# 2_PowerPerif.net
KiCad netlist of a schematic drawn in Altium Designer
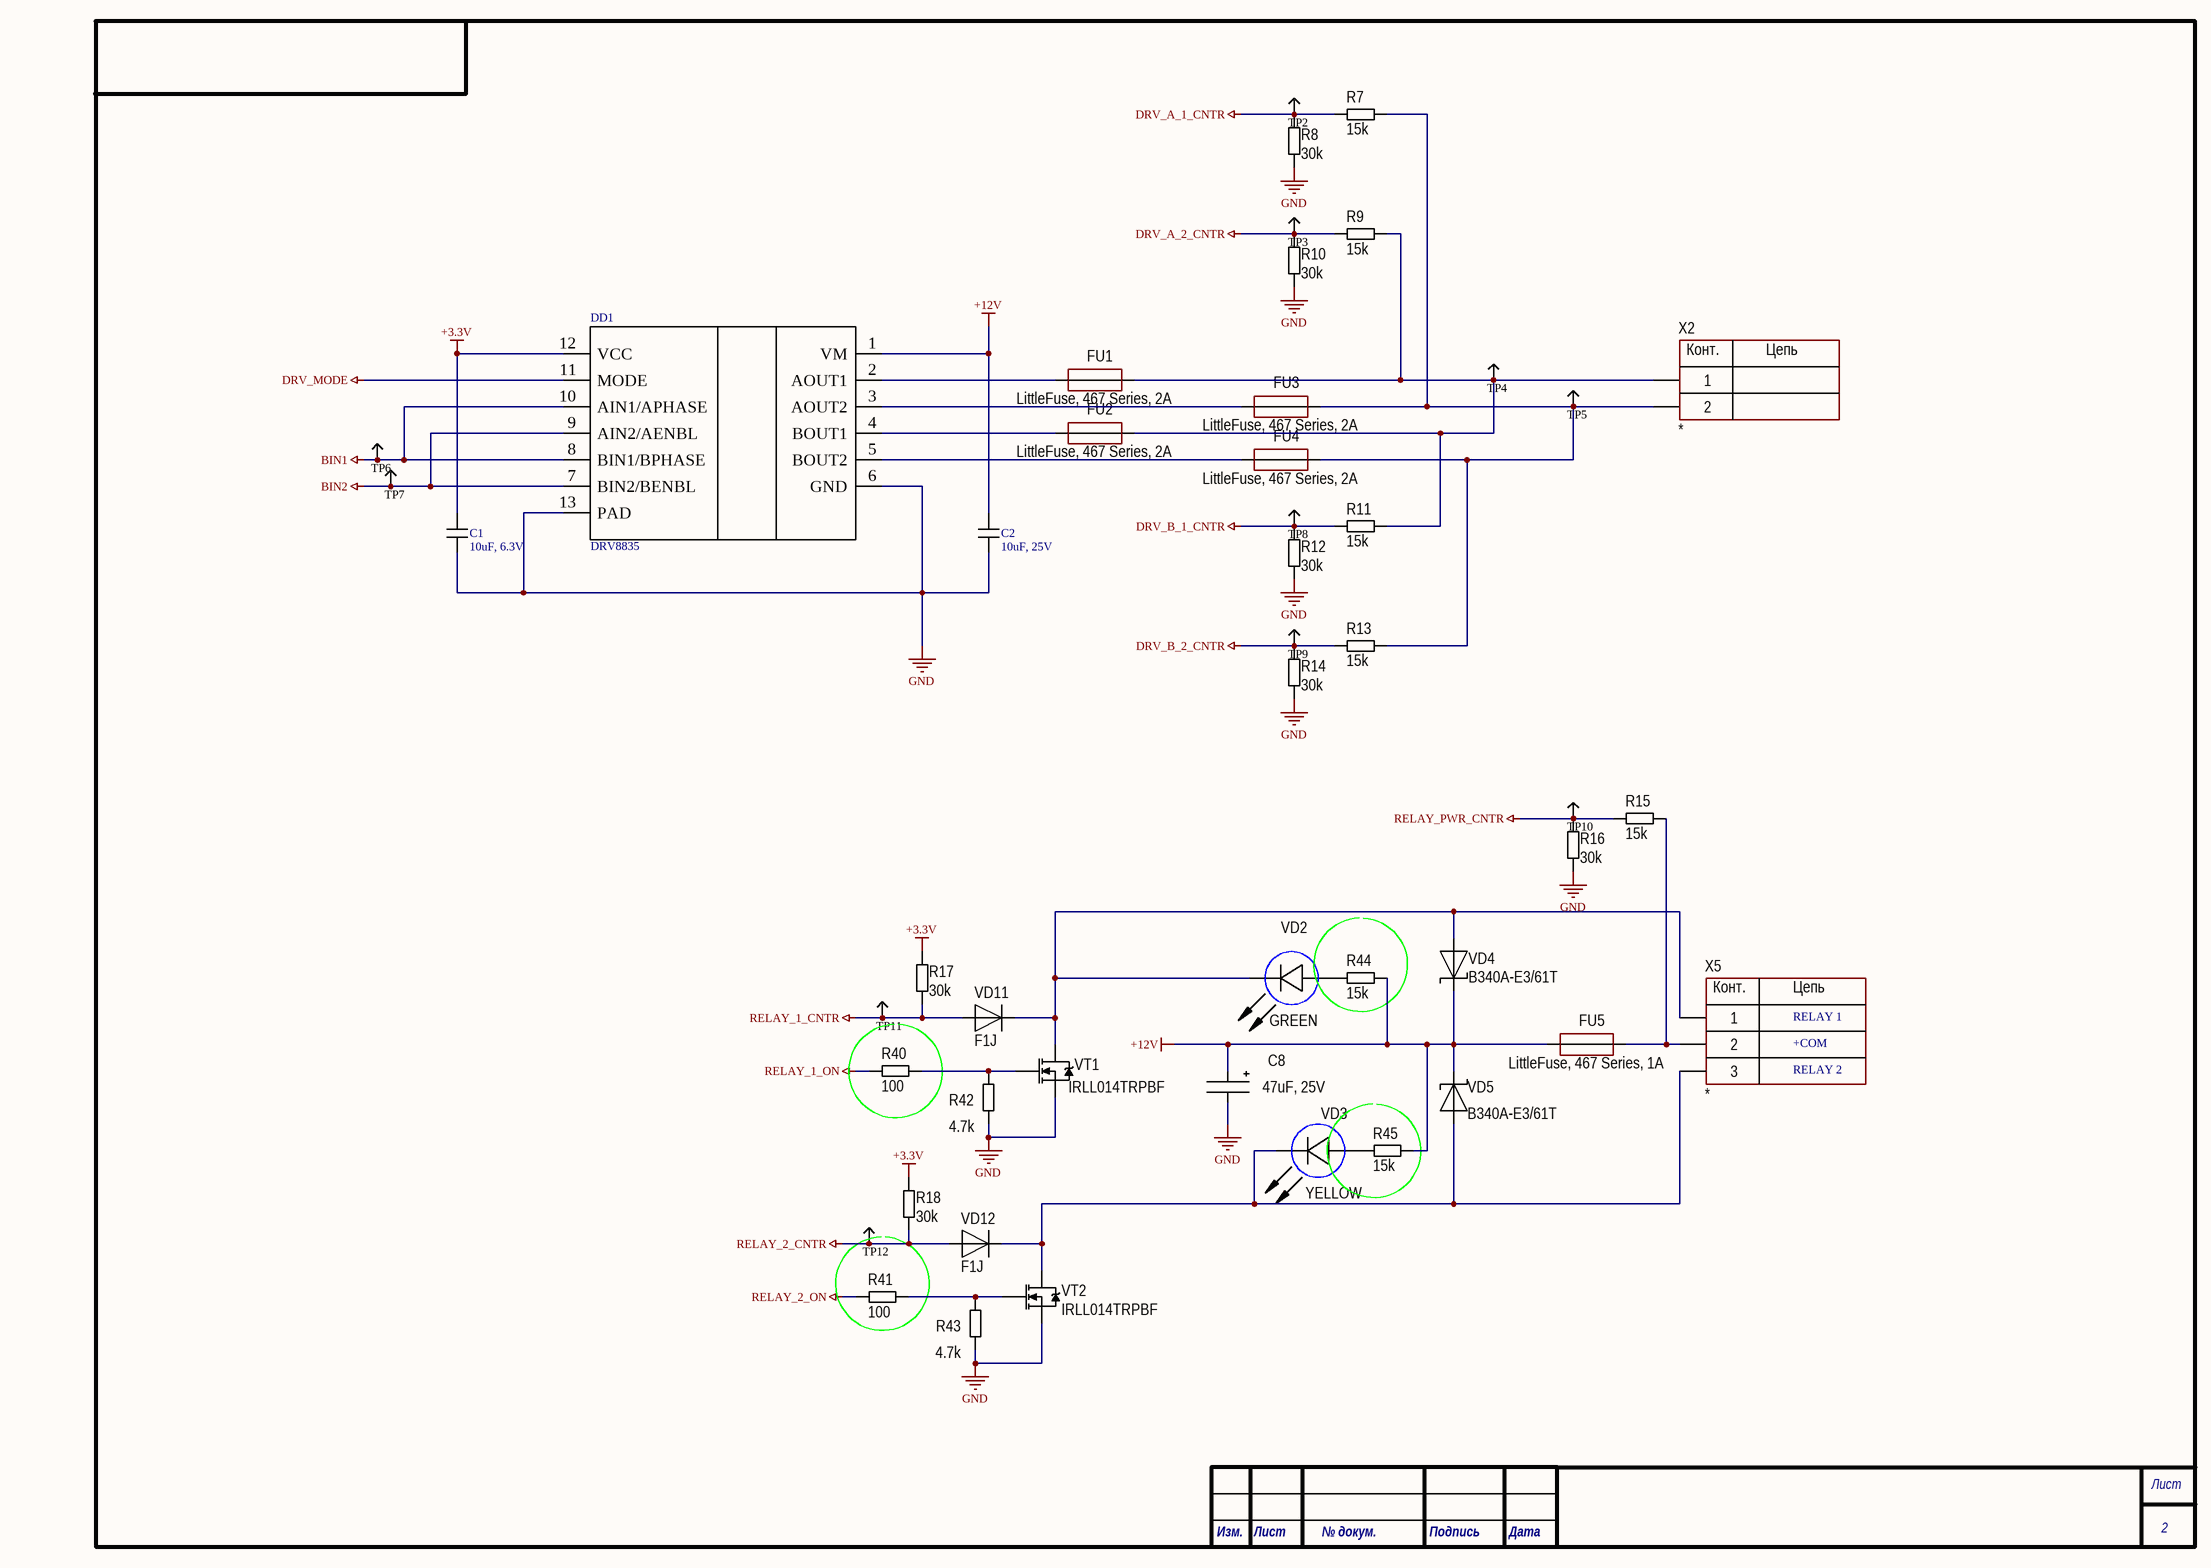
[diagram p0: 2_PowerPerif.SchDoc]

(export (version "E")
  (design (tool "Eeschema 10.0.6"))
  (components
    (comp (ref "C1")
      (value "10uF, 6.3V")
      (footprint "C_0603")
      (libsource (lib "Condensators") (part "C_SMD"))
    )
    (comp (ref "C2") (value "10uF, 25V") (footprint "C_0603") (libsource (lib "Condensators") (part "C_SMD")))
    (comp (ref "C8")
      (value "47uF, 25V")
      (footprint "D8C3.2H12")
      (libsource (lib "Condensators") (part "AlumCap"))
    )
    (comp (ref "DD1")
      (value "DRV8835")
      (footprint "WSON12")
      (description "Driver")
      (libsource (lib "MicroIC") (part "DRV8835"))
    )
    (comp (ref "FU1")
      (value "LittleFuse, 467 Series, 2A")
      (footprint "CH0603F")
      (libsource (lib "Melochi") (part "Fuse"))
    )
    (comp (ref "FU2")
      (value "LittleFuse, 467 Series, 2A")
      (footprint "CH0603F")
      (libsource (lib "Melochi") (part "Fuse"))
    )
    (comp (ref "FU3")
      (value "LittleFuse, 467 Series, 2A")
      (footprint "CH0603F")
      (libsource (lib "Melochi") (part "Fuse"))
    )
    (comp (ref "FU4")
      (value "LittleFuse, 467 Series, 2A")
      (footprint "CH0603F")
      (libsource (lib "Melochi") (part "Fuse"))
    )
    (comp (ref "FU5")
      (value "LittleFuse, 467 Series, 1A")
      (footprint "CH0603F")
      (libsource (lib "Melochi") (part "Fuse"))
    )
    (comp (ref "R7") (value "15k") (footprint "CH0603R") (libsource (lib "Resistors") (part "Resistor")))
    (comp (ref "R8") (value "30k") (footprint "CH0603R") (libsource (lib "Resistors") (part "Resistor")))
    (comp (ref "R9") (value "15k") (footprint "CH0603R") (libsource (lib "Resistors") (part "Resistor")))
    (comp (ref "R10") (value "30k") (footprint "CH0603R") (libsource (lib "Resistors") (part "Resistor")))
    (comp (ref "R11") (value "15k") (footprint "CH0603R") (libsource (lib "Resistors") (part "Resistor")))
    (comp (ref "R12") (value "30k") (footprint "CH0603R") (libsource (lib "Resistors") (part "Resistor")))
    (comp (ref "R13") (value "15k") (footprint "CH0603R") (libsource (lib "Resistors") (part "Resistor")))
    (comp (ref "R14") (value "30k") (footprint "CH0603R") (libsource (lib "Resistors") (part "Resistor")))
    (comp (ref "R15") (value "15k") (footprint "CH0603R") (libsource (lib "Resistors") (part "Resistor")))
    (comp (ref "R16") (value "30k") (footprint "CH0603R") (libsource (lib "Resistors") (part "Resistor")))
    (comp (ref "R17") (value "30k") (footprint "CH0603R") (libsource (lib "Resistors") (part "Resistor")))
    (comp (ref "R18") (value "30k") (footprint "CH0603R") (libsource (lib "Resistors") (part "Resistor")))
    (comp (ref "R40") (value "100") (footprint "CH0805R") (libsource (lib "Resistors") (part "Resistor")))
    (comp (ref "R41") (value "100") (footprint "CH0805R") (libsource (lib "Resistors") (part "Resistor")))
    (comp (ref "R42") (value "4.7k") (footprint "CH0603R") (libsource (lib "Resistors") (part "Resistor")))
    (comp (ref "R43") (value "4.7k") (footprint "CH0603R") (libsource (lib "Resistors") (part "Resistor")))
    (comp (ref "R44") (value "15k") (footprint "CH0805R") (libsource (lib "Resistors") (part "Resistor")))
    (comp (ref "R45") (value "15k") (footprint "CH0805R") (libsource (lib "Resistors") (part "Resistor")))
    (comp (ref "TP2") (value "~") (footprint "TestPoint") (libsource (lib "Melochi") (part "TestPoint")))
    (comp (ref "TP3") (value "~") (footprint "TestPoint") (libsource (lib "Melochi") (part "TestPoint")))
    (comp (ref "TP4") (value "~") (footprint "TestPoint") (libsource (lib "Melochi") (part "TestPoint")))
    (comp (ref "TP5") (value "~") (footprint "TestPoint") (libsource (lib "Melochi") (part "TestPoint")))
    (comp (ref "TP6") (value "~") (footprint "TestPoint") (libsource (lib "Melochi") (part "TestPoint")))
    (comp (ref "TP7") (value "~") (footprint "TestPoint") (libsource (lib "Melochi") (part "TestPoint")))
    (comp (ref "TP8") (value "~") (footprint "TestPoint") (libsource (lib "Melochi") (part "TestPoint")))
    (comp (ref "TP9") (value "~") (footprint "TestPoint") (libsource (lib "Melochi") (part "TestPoint")))
    (comp (ref "TP10") (value "~") (footprint "TestPoint") (libsource (lib "Melochi") (part "TestPoint")))
    (comp (ref "TP11") (value "~") (footprint "TestPoint") (libsource (lib "Melochi") (part "TestPoint")))
    (comp (ref "TP12") (value "~") (footprint "TestPoint") (libsource (lib "Melochi") (part "TestPoint")))
    (comp (ref "VD2") (value "GREEN") (footprint "CH0603LB") (libsource (lib "Diods") (part "LED_1")))
    (comp (ref "VD3") (value "YELLOW") (footprint "CH0603LB") (libsource (lib "Diods") (part "LED_1")))
    (comp (ref "VD4")
      (value "B340A-E3/61T")
      (footprint "SMA")
      (libsource (lib "Diods") (part "Diod Schottky"))
    )
    (comp (ref "VD5")
      (value "B340A-E3/61T")
      (footprint "SMA")
      (libsource (lib "Diods") (part "Diod Schottky"))
    )
    (comp (ref "VD11") (value "F1J") (footprint "SOD123F") (libsource (lib "Diods") (part "Diod")))
    (comp (ref "VD12") (value "F1J") (footprint "SOD123F") (libsource (lib "Diods") (part "Diod")))
    (comp (ref "VT1")
      (value "IRLL014TRPBF")
      (footprint "SOT223")
      (description "Mosfet")
      (libsource (lib "Tranzistor") (part "N-chanel"))
    )
    (comp (ref "VT2")
      (value "IRLL014TRPBF")
      (footprint "SOT223")
      (description "Mosfet")
      (libsource (lib "Tranzistor") (part "N-chanel"))
    )
    (comp (ref "X2") (value "*") (footprint "CON: CWF-2") (libsource (lib "Connectors") (part "2-Connector")))
    (comp (ref "X5")
      (value "*")
      (footprint "CON: 300-03P-5.0")
      (libsource (lib "Connectors") (part "3-Connector"))
    )
  )
  (nets
    (net (code "1") (name "+3.3V") (class "Default")
      (node (ref "C1") (pin "2") (pinfunction "2_2") (pintype "passive"))
      (node (ref "DD1") (pin "12") (pinfunction "VCC_12") (pintype "passive"))
      (node (ref "R17") (pin "2") (pinfunction "2_2") (pintype "passive"))
      (node (ref "R18") (pin "2") (pinfunction "2_2") (pintype "passive"))
    )
    (net (code "2") (name "+12V") (class "Default")
      (node (ref "C2") (pin "2") (pinfunction "2_2") (pintype "passive"))
      (node (ref "C8") (pin "1") (pinfunction "1_1") (pintype "power_in"))
      (node (ref "DD1") (pin "1") (pinfunction "VM_1") (pintype "passive"))
      (node (ref "FU5") (pin "1") (pinfunction "1_1") (pintype "passive"))
      (node (ref "R44") (pin "2") (pinfunction "2_2") (pintype "passive"))
      (node (ref "R45") (pin "2") (pinfunction "2_2") (pintype "passive"))
      (node (ref "VD4") (pin "2") (pinfunction "2_2") (pintype "passive"))
      (node (ref "VD5") (pin "2") (pinfunction "2_2") (pintype "passive"))
    )
    (net (code "3") (name "BIN1") (class "Default")
      (node (ref "DD1") (pin "10") (pinfunction "AIN1/APHASE_10") (pintype "passive"))
      (node (ref "DD1") (pin "8") (pinfunction "BIN1/BPHASE_8") (pintype "passive"))
      (node (ref "TP6") (pin "0") (pinfunction "0_0") (pintype "passive"))
    )
    (net (code "4") (name "BIN2") (class "Default")
      (node (ref "DD1") (pin "7") (pinfunction "BIN2/BENBL_7") (pintype "passive"))
      (node (ref "DD1") (pin "9") (pinfunction "AIN2/AENBL_9") (pintype "passive"))
      (node (ref "TP7") (pin "0") (pinfunction "0_0") (pintype "passive"))
    )
    (net (code "5") (name "DRV_A_1_CNTR") (class "Default")
      (node (ref "R7") (pin "1") (pinfunction "1_1") (pintype "passive"))
      (node (ref "R8") (pin "2") (pinfunction "2_2") (pintype "passive"))
      (node (ref "TP2") (pin "0") (pinfunction "0_0") (pintype "passive"))
    )
    (net (code "6") (name "DRV_A_2_CNTR") (class "Default")
      (node (ref "R10") (pin "2") (pinfunction "2_2") (pintype "passive"))
      (node (ref "R9") (pin "1") (pinfunction "1_1") (pintype "passive"))
      (node (ref "TP3") (pin "0") (pinfunction "0_0") (pintype "passive"))
    )
    (net (code "7") (name "DRV_B_1_CNTR") (class "Default")
      (node (ref "R11") (pin "1") (pinfunction "1_1") (pintype "passive"))
      (node (ref "R12") (pin "2") (pinfunction "2_2") (pintype "passive"))
      (node (ref "TP8") (pin "0") (pinfunction "0_0") (pintype "passive"))
    )
    (net (code "8") (name "DRV_B_2_CNTR") (class "Default")
      (node (ref "R13") (pin "1") (pinfunction "1_1") (pintype "passive"))
      (node (ref "R14") (pin "2") (pinfunction "2_2") (pintype "passive"))
      (node (ref "TP9") (pin "0") (pinfunction "0_0") (pintype "passive"))
    )
    (net (code "9") (name "DRV_MODE") (class "Default")
      (node (ref "DD1") (pin "11") (pinfunction "MODE_11") (pintype "passive"))
    )
    (net (code "10") (name "GND") (class "Default")
      (node (ref "C1") (pin "1") (pinfunction "1_1") (pintype "passive"))
      (node (ref "C2") (pin "1") (pinfunction "1_1") (pintype "passive"))
      (node (ref "C8") (pin "2") (pinfunction "2_2") (pintype "power_in"))
      (node (ref "DD1") (pin "13") (pinfunction "PAD_13") (pintype "passive"))
      (node (ref "DD1") (pin "6") (pinfunction "GND_6") (pintype "passive"))
      (node (ref "R10") (pin "1") (pinfunction "1_1") (pintype "passive"))
      (node (ref "R12") (pin "1") (pinfunction "1_1") (pintype "passive"))
      (node (ref "R14") (pin "1") (pinfunction "1_1") (pintype "passive"))
      (node (ref "R16") (pin "1") (pinfunction "1_1") (pintype "passive"))
      (node (ref "R42") (pin "1") (pinfunction "1_1") (pintype "passive"))
      (node (ref "R43") (pin "1") (pinfunction "1_1") (pintype "passive"))
      (node (ref "R8") (pin "1") (pinfunction "1_1") (pintype "passive"))
      (node (ref "VT1") (pin "3") (pinfunction "S_3") (pintype "passive"))
      (node (ref "VT2") (pin "3") (pinfunction "S_3") (pintype "passive"))
    )
    (net (code "11") (name "Net-(DD1-AOUT1)") (class "Default")
      (node (ref "DD1") (pin "2") (pinfunction "AOUT1_2") (pintype "passive"))
      (node (ref "FU1") (pin "1") (pinfunction "1_1") (pintype "passive"))
    )
    (net (code "12") (name "Net-(DD1-AOUT2)") (class "Default")
      (node (ref "DD1") (pin "3") (pinfunction "AOUT2_3") (pintype "passive"))
      (node (ref "FU3") (pin "1") (pinfunction "1_1") (pintype "passive"))
    )
    (net (code "13") (name "Net-(DD1-BOUT1)") (class "Default")
      (node (ref "DD1") (pin "4") (pinfunction "BOUT1_4") (pintype "passive"))
      (node (ref "FU2") (pin "1") (pinfunction "1_1") (pintype "passive"))
    )
    (net (code "14") (name "Net-(DD1-BOUT2)") (class "Default")
      (node (ref "DD1") (pin "5") (pinfunction "BOUT2_5") (pintype "passive"))
      (node (ref "FU4") (pin "1") (pinfunction "1_1") (pintype "passive"))
    )
    (net (code "15") (name "Net-(FU1-Pad2)") (class "Default")
      (node (ref "FU1") (pin "2") (pinfunction "2_2") (pintype "passive"))
      (node (ref "FU2") (pin "2") (pinfunction "2_2") (pintype "passive"))
      (node (ref "R11") (pin "2") (pinfunction "2_2") (pintype "passive"))
      (node (ref "R9") (pin "2") (pinfunction "2_2") (pintype "passive"))
      (node (ref "TP4") (pin "0") (pinfunction "0_0") (pintype "passive"))
      (node (ref "X2") (pin "1") (pinfunction "1_1") (pintype "passive"))
    )
    (net (code "16") (name "Net-(FU3-Pad2)") (class "Default")
      (node (ref "FU3") (pin "2") (pinfunction "2_2") (pintype "passive"))
      (node (ref "FU4") (pin "2") (pinfunction "2_2") (pintype "passive"))
      (node (ref "R13") (pin "2") (pinfunction "2_2") (pintype "passive"))
      (node (ref "R7") (pin "2") (pinfunction "2_2") (pintype "passive"))
      (node (ref "TP5") (pin "0") (pinfunction "0_0") (pintype "passive"))
      (node (ref "X2") (pin "2") (pinfunction "2_2") (pintype "passive"))
    )
    (net (code "17") (name "Net-(FU5-Pad2)") (class "Default")
      (node (ref "FU5") (pin "2") (pinfunction "2_2") (pintype "passive"))
      (node (ref "R15") (pin "2") (pinfunction "2_2") (pintype "passive"))
      (node (ref "X5") (pin "2") (pinfunction "2_2") (pintype "passive"))
    )
    (net (code "18") (name "Net-(VD2-A)") (class "Default")
      (node (ref "R44") (pin "1") (pinfunction "1_1") (pintype "passive"))
      (node (ref "VD2") (pin "1") (pinfunction "A_1") (pintype "passive"))
    )
    (net (code "19") (name "Net-(VD2-C)") (class "Default")
      (node (ref "VD11") (pin "2") (pinfunction "2_2") (pintype "passive"))
      (node (ref "VD2") (pin "2") (pinfunction "C_2") (pintype "passive"))
      (node (ref "VD4") (pin "1") (pinfunction "1_1") (pintype "passive"))
      (node (ref "VT1") (pin "2") (pinfunction "D_2") (pintype "passive"))
      (node (ref "X5") (pin "1") (pinfunction "1_1") (pintype "passive"))
    )
    (net (code "20") (name "Net-(VD3-A)") (class "Default")
      (node (ref "R45") (pin "1") (pinfunction "1_1") (pintype "passive"))
      (node (ref "VD3") (pin "1") (pinfunction "A_1") (pintype "passive"))
    )
    (net (code "21") (name "Net-(VD3-C)") (class "Default")
      (node (ref "VD12") (pin "2") (pinfunction "2_2") (pintype "passive"))
      (node (ref "VD3") (pin "2") (pinfunction "C_2") (pintype "passive"))
      (node (ref "VD5") (pin "1") (pinfunction "1_1") (pintype "passive"))
      (node (ref "VT2") (pin "2") (pinfunction "D_2") (pintype "passive"))
      (node (ref "X5") (pin "3") (pinfunction "3_3") (pintype "passive"))
    )
    (net (code "22") (name "Net-(VT1-G)") (class "Default")
      (node (ref "R40") (pin "1") (pinfunction "1_1") (pintype "passive"))
      (node (ref "R42") (pin "2") (pinfunction "2_2") (pintype "passive"))
      (node (ref "VT1") (pin "1") (pinfunction "G_1") (pintype "passive"))
    )
    (net (code "23") (name "Net-(VT2-G)") (class "Default")
      (node (ref "R41") (pin "1") (pinfunction "1_1") (pintype "passive"))
      (node (ref "R43") (pin "2") (pinfunction "2_2") (pintype "passive"))
      (node (ref "VT2") (pin "1") (pinfunction "G_1") (pintype "passive"))
    )
    (net (code "24") (name "RELAY_1_CNTR") (class "Default")
      (node (ref "R17") (pin "1") (pinfunction "1_1") (pintype "passive"))
      (node (ref "TP11") (pin "0") (pinfunction "0_0") (pintype "passive"))
      (node (ref "VD11") (pin "1") (pinfunction "1_1") (pintype "passive"))
    )
    (net (code "25") (name "RELAY_1_ON") (class "Default")
      (node (ref "R40") (pin "2") (pinfunction "2_2") (pintype "passive"))
    )
    (net (code "26") (name "RELAY_2_CNTR") (class "Default")
      (node (ref "R18") (pin "1") (pinfunction "1_1") (pintype "passive"))
      (node (ref "TP12") (pin "0") (pinfunction "0_0") (pintype "passive"))
      (node (ref "VD12") (pin "1") (pinfunction "1_1") (pintype "passive"))
    )
    (net (code "27") (name "RELAY_2_ON") (class "Default")
      (node (ref "R41") (pin "2") (pinfunction "2_2") (pintype "passive"))
    )
    (net (code "28") (name "RELAY_PWR_CNTR") (class "Default")
      (node (ref "R15") (pin "1") (pinfunction "1_1") (pintype "passive"))
      (node (ref "R16") (pin "2") (pinfunction "2_2") (pintype "passive"))
      (node (ref "TP10") (pin "0") (pinfunction "0_0") (pintype "passive"))
    )
  )
)
